# Dashboard_rev5.net
KiCad netlist of a schematic drawn in EAGLE
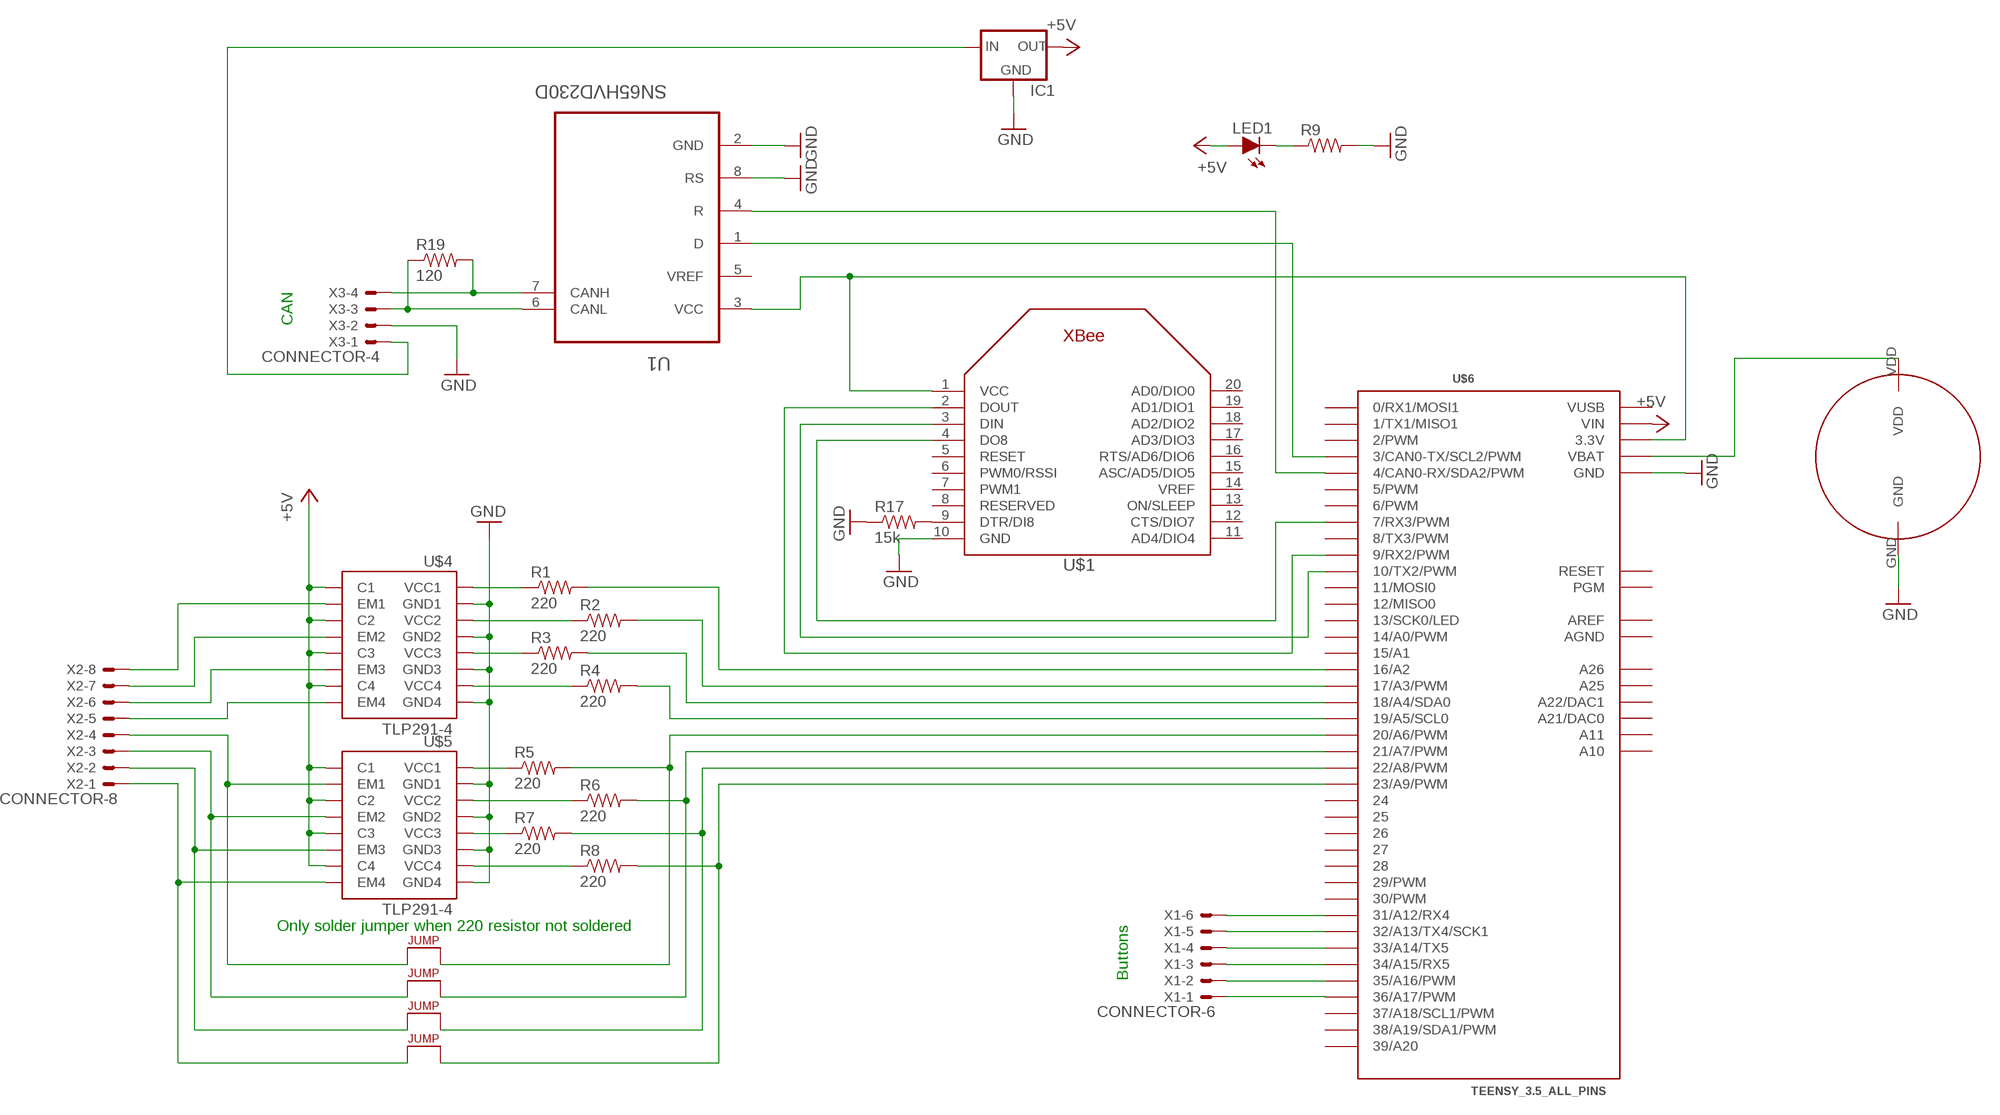
[diagram p0: schematic, sheet 1]

(export (version "E")
  (design (tool "Eeschema 10.0.6"))
  (components
    (comp (ref "BATT")
      (value "COIN-CELL-HOLDER")
      (footprint "eagle-import:COIN-CELL-HOLDER")
      (libsource (lib "eagle-import") (part "COIN-CELL-HOLDER"))
    )
    (comp (ref "IC1")
      (value "5VREG_L7805SPACED")
      (footprint "eagle-import:TO-220-SPACED")
      (libsource (lib "eagle-import") (part "5VREG_L7805SPACED"))
    )
    (comp (ref "LED1")
      (value "LED-0805")
      (footprint "eagle-import:LED-805")
      (libsource (lib "eagle-import") (part "LED-0805"))
    )
    (comp (ref "R1")
      (value "220")
      (footprint "eagle-import:0805")
      (libsource (lib "eagle-import") (part "RESISTOR0805-RES"))
    )
    (comp (ref "R2")
      (value "220")
      (footprint "eagle-import:0805")
      (libsource (lib "eagle-import") (part "RESISTOR0805-RES"))
    )
    (comp (ref "R3")
      (value "220")
      (footprint "eagle-import:0805")
      (libsource (lib "eagle-import") (part "RESISTOR0805-RES"))
    )
    (comp (ref "R4")
      (value "220")
      (footprint "eagle-import:0805")
      (libsource (lib "eagle-import") (part "RESISTOR0805-RES"))
    )
    (comp (ref "R5")
      (value "220")
      (footprint "eagle-import:0805")
      (libsource (lib "eagle-import") (part "RESISTOR0805-RES"))
    )
    (comp (ref "R6")
      (value "220")
      (footprint "eagle-import:0805")
      (libsource (lib "eagle-import") (part "RESISTOR0805-RES"))
    )
    (comp (ref "R7")
      (value "220")
      (footprint "eagle-import:0805")
      (libsource (lib "eagle-import") (part "RESISTOR0805-RES"))
    )
    (comp (ref "R8")
      (value "220")
      (footprint "eagle-import:0805")
      (libsource (lib "eagle-import") (part "RESISTOR0805-RES"))
    )
    (comp (ref "R9")
      (value "RESISTOR0805-RES")
      (footprint "eagle-import:0805")
      (libsource (lib "eagle-import") (part "RESISTOR0805-RES"))
    )
    (comp (ref "R17")
      (value "15k")
      (footprint "eagle-import:0805")
      (libsource (lib "eagle-import") (part "RESISTOR0805-RES"))
    )
    (comp (ref "R19")
      (value "120")
      (footprint "eagle-import:0805")
      (libsource (lib "eagle-import") (part "RESISTOR0805-RES"))
    )
    (comp (ref "U$1")
      (value "XBEE")
      (footprint "eagle-import:XBEE")
      (libsource (lib "eagle-import") (part "XBEE"))
    )
    (comp (ref "U$3")
      (value "JUMPER")
      (footprint "eagle-import:0805")
      (libsource (lib "eagle-import") (part "JUMPER"))
    )
    (comp (ref "U$4")
      (value "TLP291-4")
      (footprint "eagle-import:SOIC-16")
      (libsource (lib "eagle-import") (part "TLP291-4"))
    )
    (comp (ref "U$5")
      (value "TLP291-4")
      (footprint "eagle-import:SOIC-16")
      (libsource (lib "eagle-import") (part "TLP291-4"))
    )
    (comp (ref "U$6")
      (value "TEENSY_3.5_ALL_PINS")
      (footprint "eagle-import:TEENSY_3.5_ALL_PINS")
      (libsource (lib "eagle-import") (part "TEENSY_3.5_ALL_PINS"))
    )
    (comp (ref "U$7")
      (value "JUMPER")
      (footprint "eagle-import:0805")
      (libsource (lib "eagle-import") (part "JUMPER"))
    )
    (comp (ref "U$8")
      (value "JUMPER")
      (footprint "eagle-import:0805")
      (libsource (lib "eagle-import") (part "JUMPER"))
    )
    (comp (ref "U$9")
      (value "JUMPER")
      (footprint "eagle-import:0805")
      (libsource (lib "eagle-import") (part "JUMPER"))
    )
    (comp (ref "U1")
      (value "SN65HVD230D")
      (footprint "eagle-import:SOIC127P600X175-8N")
      (libsource (lib "eagle-import") (part "SN65HVD230D"))
    )
    (comp (ref "X1")
      (value "CONNECTOR-6")
      (footprint "eagle-import:MINIFIT_5566-6")
      (fields (field (name "MPN") "95566-61002"))
      (libsource (lib "eagle-import") (part "CONNECTOR-6"))
    )
    (comp (ref "X2")
      (value "CONNECTOR-8")
      (footprint "eagle-import:MINIFIT_5566-8")
      (libsource (lib "eagle-import") (part "CONNECTOR-8"))
    )
    (comp (ref "X3")
      (value "CONNECTOR-4")
      (footprint "eagle-import:MINIFIT_5566-4")
      (libsource (lib "eagle-import") (part "CONNECTOR-4"))
    )
  )
  (nets
    (net (code "1") (name "+5V") (class "Default")
      (node (ref "IC1") (pin "3") (pinfunction "OUT_3") (pintype "output"))
      (node (ref "LED1") (pin "A") (pinfunction "A_A") (pintype "passive"))
      (node (ref "U$4") (pin "10") (pinfunction "C4_10") (pintype "passive"))
      (node (ref "U$4") (pin "12") (pinfunction "C3_12") (pintype "passive"))
      (node (ref "U$4") (pin "14") (pinfunction "C2_14") (pintype "passive"))
      (node (ref "U$4") (pin "16") (pinfunction "C1_16") (pintype "passive"))
      (node (ref "U$5") (pin "10") (pinfunction "C4_10") (pintype "passive"))
      (node (ref "U$5") (pin "12") (pinfunction "C3_12") (pintype "passive"))
      (node (ref "U$5") (pin "14") (pinfunction "C2_14") (pintype "passive"))
      (node (ref "U$5") (pin "16") (pinfunction "C1_16") (pintype "passive"))
      (node (ref "U$6") (pin "VIN") (pinfunction "VIN_VIN") (pintype "power_in"))
    )
    (net (code "2") (name "/AGND") (class "Default")
      (node (ref "U$6") (pin "AGND") (pinfunction "AGND_AGND") (pintype "power_in"))
    )
    (net (code "3") (name "/AREF") (class "Default")
      (node (ref "U$6") (pin "AREF") (pinfunction "AREF_AREF") (pintype "power_in"))
    )
    (net (code "4") (name "/VUSB") (class "Default")
      (node (ref "U$6") (pin "VUSB") (pinfunction "VUSB_VUSB") (pintype "power_in"))
    )
    (net (code "5") (name "GND") (class "Default")
      (node (ref "BATT") (pin "GND") (pinfunction "GND_GND") (pintype "bidirectional"))
      (node (ref "IC1") (pin "2") (pinfunction "GND_2") (pintype "input"))
      (node (ref "R17") (pin "1") (pinfunction "1_1") (pintype "passive"))
      (node (ref "R9") (pin "2") (pinfunction "2_2") (pintype "passive"))
      (node (ref "U$1") (pin "10") (pinfunction "GND_10") (pintype "power_in"))
      (node (ref "U$4") (pin "2") (pinfunction "GND1_2") (pintype "passive"))
      (node (ref "U$4") (pin "4") (pinfunction "GND2_4") (pintype "passive"))
      (node (ref "U$4") (pin "6") (pinfunction "GND3_6") (pintype "passive"))
      (node (ref "U$4") (pin "8") (pinfunction "GND4_8") (pintype "passive"))
      (node (ref "U$5") (pin "2") (pinfunction "GND1_2") (pintype "passive"))
      (node (ref "U$5") (pin "4") (pinfunction "GND2_4") (pintype "passive"))
      (node (ref "U$5") (pin "6") (pinfunction "GND3_6") (pintype "passive"))
      (node (ref "U$5") (pin "8") (pinfunction "GND4_8") (pintype "passive"))
      (node (ref "U$6") (pin "GND") (pinfunction "GND_GND") (pintype "power_in"))
      (node (ref "U$6") (pin "GND1") (pinfunction "GND_GND1") (pintype "power_in"))
      (node (ref "U$6") (pin "GND3") (pinfunction "GND_GND3") (pintype "power_in"))
      (node (ref "U$6") (pin "GND4") (pinfunction "GND_GND4") (pintype "power_in"))
      (node (ref "U$6") (pin "GND6") (pinfunction "GND_GND6") (pintype "power_in"))
      (node (ref "U1") (pin "2") (pinfunction "GND_2") (pintype "passive"))
      (node (ref "U1") (pin "8") (pinfunction "RS_8") (pintype "input"))
      (node (ref "X3") (pin "2") (pinfunction "S_2") (pintype "passive"))
    )
    (net (code "6") (name "Net-(BATT-PadVDD)") (class "Default")
      (node (ref "BATT") (pin "VDD") (pinfunction "VDD_VDD") (pintype "bidirectional"))
      (node (ref "U$6") (pin "VBAT") (pinfunction "VBAT_VBAT") (pintype "power_in"))
    )
    (net (code "7") (name "Net-(IC1-IN)") (class "Default")
      (node (ref "IC1") (pin "1") (pinfunction "IN_1") (pintype "input"))
      (node (ref "X3") (pin "1") (pinfunction "S_1") (pintype "passive"))
    )
    (net (code "8") (name "Net-(LED1-PadC)") (class "Default")
      (node (ref "LED1") (pin "C") (pinfunction "C_C") (pintype "passive"))
      (node (ref "R9") (pin "1") (pinfunction "1_1") (pintype "passive"))
    )
    (net (code "9") (name "Net-(R1-Pad2)") (class "Default")
      (node (ref "R1") (pin "2") (pinfunction "2_2") (pintype "passive"))
      (node (ref "U$6") (pin "16/A2") (pinfunction "16/A2_16/A2") (pintype "bidirectional"))
    )
    (net (code "10") (name "Net-(U$1-DIN)") (class "Default")
      (node (ref "U$1") (pin "3") (pinfunction "DIN_3") (pintype "input"))
      (node (ref "U$6") (pin "10") (pinfunction "10/TX2/PWM_10") (pintype "bidirectional"))
    )
    (net (code "11") (name "Net-(U$1-DO8)") (class "Default")
      (node (ref "U$1") (pin "4") (pinfunction "DO8_4") (pintype "output"))
      (node (ref "U$6") (pin "7") (pinfunction "7/RX3/PWM_7") (pintype "bidirectional"))
    )
    (net (code "12") (name "Net-(U$1-DOUT)") (class "Default")
      (node (ref "U$1") (pin "2") (pinfunction "DOUT_2") (pintype "output"))
      (node (ref "U$6") (pin "9") (pinfunction "9/RX2/PWM_9") (pintype "bidirectional"))
    )
    (net (code "13") (name "Net-(U$1-DTR{slash}DI8)") (class "Default")
      (node (ref "R17") (pin "2") (pinfunction "2_2") (pintype "passive"))
      (node (ref "U$1") (pin "9") (pinfunction "DTR/DI8_9") (pintype "input"))
    )
    (net (code "14") (name "Net-(U$1-VCC)") (class "Default")
      (node (ref "U$1") (pin "1") (pinfunction "VCC_1") (pintype "power_in"))
      (node (ref "U$6") (pin "3.3V") (pinfunction "3.3V_3.3V") (pintype "power_in"))
      (node (ref "U$6") (pin "3.3V3") (pinfunction "3.3V_3.3V3") (pintype "power_in"))
      (node (ref "U$6") (pin "3.3V4") (pinfunction "3.3V_3.3V4") (pintype "power_in"))
      (node (ref "U1") (pin "3") (pinfunction "VCC_3") (pintype "power_in"))
    )
    (net (code "15") (name "Net-(U$3-P$1)") (class "Default")
      (node (ref "U$3") (pin "1") (pinfunction "P$1_1") (pintype "bidirectional"))
      (node (ref "U$5") (pin "15") (pinfunction "EM1_15") (pintype "passive"))
      (node (ref "X2") (pin "4") (pinfunction "S_4") (pintype "passive"))
    )
    (net (code "16") (name "Net-(U$3-P$2)") (class "Default")
      (node (ref "R5") (pin "2") (pinfunction "2_2") (pintype "passive"))
      (node (ref "U$3") (pin "2") (pinfunction "P$2_2") (pintype "bidirectional"))
      (node (ref "U$6") (pin "20/A6") (pinfunction "20/A6/PWM_20/A6") (pintype "bidirectional"))
    )
    (net (code "17") (name "Net-(U$4-EM1)") (class "Default")
      (node (ref "U$4") (pin "15") (pinfunction "EM1_15") (pintype "passive"))
      (node (ref "X2") (pin "8") (pinfunction "S_8") (pintype "passive"))
    )
    (net (code "18") (name "Net-(U$4-EM2)") (class "Default")
      (node (ref "U$4") (pin "13") (pinfunction "EM2_13") (pintype "passive"))
      (node (ref "X2") (pin "7") (pinfunction "S_7") (pintype "passive"))
    )
    (net (code "19") (name "Net-(U$4-EM3)") (class "Default")
      (node (ref "U$4") (pin "11") (pinfunction "EM3_11") (pintype "passive"))
      (node (ref "X2") (pin "6") (pinfunction "S_6") (pintype "passive"))
    )
    (net (code "20") (name "Net-(U$4-EM4)") (class "Default")
      (node (ref "U$4") (pin "9") (pinfunction "EM4_9") (pintype "passive"))
      (node (ref "X2") (pin "5") (pinfunction "S_5") (pintype "passive"))
    )
    (net (code "21") (name "Net-(U$4-VCC1)") (class "Default")
      (node (ref "R1") (pin "1") (pinfunction "1_1") (pintype "passive"))
      (node (ref "U$4") (pin "1") (pinfunction "VCC1_1") (pintype "passive"))
    )
    (net (code "22") (name "Net-(U$4-VCC2)") (class "Default")
      (node (ref "R2") (pin "1") (pinfunction "1_1") (pintype "passive"))
      (node (ref "U$4") (pin "3") (pinfunction "VCC2_3") (pintype "passive"))
    )
    (net (code "23") (name "Net-(U$4-VCC3)") (class "Default")
      (node (ref "R3") (pin "1") (pinfunction "1_1") (pintype "passive"))
      (node (ref "U$4") (pin "5") (pinfunction "VCC3_5") (pintype "passive"))
    )
    (net (code "24") (name "Net-(U$4-VCC4)") (class "Default")
      (node (ref "R4") (pin "1") (pinfunction "1_1") (pintype "passive"))
      (node (ref "U$4") (pin "7") (pinfunction "VCC4_7") (pintype "passive"))
    )
    (net (code "25") (name "Net-(U$5-EM2)") (class "Default")
      (node (ref "U$5") (pin "13") (pinfunction "EM2_13") (pintype "passive"))
      (node (ref "U$7") (pin "1") (pinfunction "P$1_1") (pintype "bidirectional"))
      (node (ref "X2") (pin "3") (pinfunction "S_3") (pintype "passive"))
    )
    (net (code "26") (name "Net-(U$5-EM3)") (class "Default")
      (node (ref "U$5") (pin "11") (pinfunction "EM3_11") (pintype "passive"))
      (node (ref "U$8") (pin "1") (pinfunction "P$1_1") (pintype "bidirectional"))
      (node (ref "X2") (pin "2") (pinfunction "S_2") (pintype "passive"))
    )
    (net (code "27") (name "Net-(U$5-EM4)") (class "Default")
      (node (ref "U$5") (pin "9") (pinfunction "EM4_9") (pintype "passive"))
      (node (ref "U$9") (pin "1") (pinfunction "P$1_1") (pintype "bidirectional"))
      (node (ref "X2") (pin "1") (pinfunction "S_1") (pintype "passive"))
    )
    (net (code "28") (name "Net-(U$5-VCC1)") (class "Default")
      (node (ref "R5") (pin "1") (pinfunction "1_1") (pintype "passive"))
      (node (ref "U$5") (pin "1") (pinfunction "VCC1_1") (pintype "passive"))
    )
    (net (code "29") (name "Net-(U$5-VCC2)") (class "Default")
      (node (ref "R6") (pin "1") (pinfunction "1_1") (pintype "passive"))
      (node (ref "U$5") (pin "3") (pinfunction "VCC2_3") (pintype "passive"))
    )
    (net (code "30") (name "Net-(U$5-VCC3)") (class "Default")
      (node (ref "R7") (pin "1") (pinfunction "1_1") (pintype "passive"))
      (node (ref "U$5") (pin "5") (pinfunction "VCC3_5") (pintype "passive"))
    )
    (net (code "31") (name "Net-(U$5-VCC4)") (class "Default")
      (node (ref "R8") (pin "1") (pinfunction "1_1") (pintype "passive"))
      (node (ref "U$5") (pin "7") (pinfunction "VCC4_7") (pintype "passive"))
    )
    (net (code "32") (name "Net-(U$6-3{slash}CAN0-TX{slash}SCL2{slash}PWM)") (class "Default")
      (node (ref "U$6") (pin "3") (pinfunction "3/CAN0-TX/SCL2/PWM_3") (pintype "bidirectional"))
      (node (ref "U1") (pin "1") (pinfunction "D_1") (pintype "input"))
    )
    (net (code "33") (name "Net-(U$6-4{slash}CAN0-RX{slash}SDA2{slash}PWM)") (class "Default")
      (node (ref "U$6") (pin "4") (pinfunction "4/CAN0-RX/SDA2/PWM_4") (pintype "bidirectional"))
      (node (ref "U1") (pin "4") (pinfunction "R_4") (pintype "input"))
    )
    (net (code "34") (name "Net-(U$6-17{slash}A3{slash}PWM)") (class "Default")
      (node (ref "R2") (pin "2") (pinfunction "2_2") (pintype "passive"))
      (node (ref "U$6") (pin "17/A3") (pinfunction "17/A3/PWM_17/A3") (pintype "bidirectional"))
    )
    (net (code "35") (name "Net-(U$6-18{slash}A4{slash}SDA0)") (class "Default")
      (node (ref "R3") (pin "2") (pinfunction "2_2") (pintype "passive"))
      (node (ref "U$6") (pin "18/A4") (pinfunction "18/A4/SDA0_18/A4") (pintype "bidirectional"))
    )
    (net (code "36") (name "Net-(U$6-19{slash}A5{slash}SCL0)") (class "Default")
      (node (ref "R4") (pin "2") (pinfunction "2_2") (pintype "passive"))
      (node (ref "U$6") (pin "19/A5") (pinfunction "19/A5/SCL0_19/A5") (pintype "bidirectional"))
    )
    (net (code "37") (name "Net-(U$6-21{slash}A7{slash}PWM)") (class "Default")
      (node (ref "R6") (pin "2") (pinfunction "2_2") (pintype "passive"))
      (node (ref "U$6") (pin "21/A7") (pinfunction "21/A7/PWM_21/A7") (pintype "bidirectional"))
      (node (ref "U$7") (pin "2") (pinfunction "P$2_2") (pintype "bidirectional"))
    )
    (net (code "38") (name "Net-(U$6-22{slash}A8{slash}PWM)") (class "Default")
      (node (ref "R7") (pin "2") (pinfunction "2_2") (pintype "passive"))
      (node (ref "U$6") (pin "22/A8") (pinfunction "22/A8/PWM_22/A8") (pintype "bidirectional"))
      (node (ref "U$8") (pin "2") (pinfunction "P$2_2") (pintype "bidirectional"))
    )
    (net (code "39") (name "Net-(U$6-23{slash}A9{slash}PWM)") (class "Default")
      (node (ref "R8") (pin "2") (pinfunction "2_2") (pintype "passive"))
      (node (ref "U$6") (pin "23/A9") (pinfunction "23/A9/PWM_23/A9") (pintype "bidirectional"))
      (node (ref "U$9") (pin "2") (pinfunction "P$2_2") (pintype "bidirectional"))
    )
    (net (code "40") (name "Net-(U$6-31{slash}A12{slash}RX4)") (class "Default")
      (node (ref "U$6") (pin "31/A12") (pinfunction "31/A12/RX4_31/A12") (pintype "bidirectional"))
      (node (ref "X1") (pin "6") (pinfunction "S_6") (pintype "passive"))
    )
    (net (code "41") (name "Net-(U$6-32{slash}A13{slash}TX4{slash}SCK1)") (class "Default")
      (node (ref "U$6") (pin "32/A13") (pinfunction "32/A13/TX4/SCK1_32/A13") (pintype "bidirectional"))
      (node (ref "X1") (pin "5") (pinfunction "S_5") (pintype "passive"))
    )
    (net (code "42") (name "Net-(U$6-33{slash}A14{slash}TX5)") (class "Default")
      (node (ref "U$6") (pin "33/A14") (pinfunction "33/A14/TX5_33/A14") (pintype "bidirectional"))
      (node (ref "X1") (pin "4") (pinfunction "S_4") (pintype "passive"))
    )
    (net (code "43") (name "Net-(U$6-34{slash}A15{slash}RX5)") (class "Default")
      (node (ref "U$6") (pin "34/A15") (pinfunction "34/A15/RX5_34/A15") (pintype "bidirectional"))
      (node (ref "X1") (pin "3") (pinfunction "S_3") (pintype "passive"))
    )
    (net (code "44") (name "Net-(U$6-35{slash}A16{slash}PWM)") (class "Default")
      (node (ref "U$6") (pin "35/A16") (pinfunction "35/A16/PWM_35/A16") (pintype "bidirectional"))
      (node (ref "X1") (pin "2") (pinfunction "S_2") (pintype "passive"))
    )
    (net (code "45") (name "Net-(U$6-36{slash}A17{slash}PWM)") (class "Default")
      (node (ref "U$6") (pin "36/A17") (pinfunction "36/A17/PWM_36/A17") (pintype "bidirectional"))
      (node (ref "X1") (pin "1") (pinfunction "S_1") (pintype "passive"))
    )
    (net (code "46") (name "Net-(U1-CANH)") (class "Default")
      (node (ref "R19") (pin "2") (pinfunction "2_2") (pintype "passive"))
      (node (ref "U1") (pin "7") (pinfunction "CANH_7") (pintype "output"))
      (node (ref "X3") (pin "4") (pinfunction "S_4") (pintype "passive"))
    )
    (net (code "47") (name "Net-(U1-CANL)") (class "Default")
      (node (ref "R19") (pin "1") (pinfunction "1_1") (pintype "passive"))
      (node (ref "U1") (pin "6") (pinfunction "CANL_6") (pintype "output"))
      (node (ref "X3") (pin "3") (pinfunction "S_3") (pintype "passive"))
    )
    (net (code "48") (name "unconnected-(U$1-AD0{slash}DIO0-Pad20)") (class "Default")
      (node (ref "U$1") (pin "20") (pinfunction "AD0/DIO0_20") (pintype "bidirectional"))
    )
    (net (code "49") (name "unconnected-(U$1-AD1{slash}DIO1-Pad19)") (class "Default")
      (node (ref "U$1") (pin "19") (pinfunction "AD1/DIO1_19") (pintype "bidirectional"))
    )
    (net (code "50") (name "unconnected-(U$1-AD2{slash}DIO2-Pad18)") (class "Default")
      (node (ref "U$1") (pin "18") (pinfunction "AD2/DIO2_18") (pintype "bidirectional"))
    )
    (net (code "51") (name "unconnected-(U$1-AD3{slash}DIO3-Pad17)") (class "Default")
      (node (ref "U$1") (pin "17") (pinfunction "AD3/DIO3_17") (pintype "bidirectional"))
    )
    (net (code "52") (name "unconnected-(U$1-AD4{slash}DIO4-Pad11)") (class "Default")
      (node (ref "U$1") (pin "11") (pinfunction "AD4/DIO4_11") (pintype "bidirectional"))
    )
    (net (code "53") (name "unconnected-(U$1-ASC{slash}AD5{slash}DIO5-Pad15)") (class "Default")
      (node (ref "U$1") (pin "15") (pinfunction "ASC/AD5/DIO5_15") (pintype "bidirectional"))
    )
    (net (code "54") (name "unconnected-(U$1-CTS{slash}DIO7-Pad12)") (class "Default")
      (node (ref "U$1") (pin "12") (pinfunction "CTS/DIO7_12") (pintype "bidirectional"))
    )
    (net (code "55") (name "unconnected-(U$1-ON{slash}SLEEP-Pad13)") (class "Default")
      (node (ref "U$1") (pin "13") (pinfunction "ON/SLEEP_13") (pintype "output"))
    )
    (net (code "56") (name "unconnected-(U$1-PWM0{slash}RSSI-Pad6)") (class "Default")
      (node (ref "U$1") (pin "6") (pinfunction "PWM0/RSSI_6") (pintype "output"))
    )
    (net (code "57") (name "unconnected-(U$1-PWM1-Pad7)") (class "Default")
      (node (ref "U$1") (pin "7") (pinfunction "PWM1_7") (pintype "output"))
    )
    (net (code "58") (name "unconnected-(U$1-RESERVED-Pad8)") (class "Default")
      (node (ref "U$1") (pin "8") (pinfunction "RESERVED_8") (pintype "no_connect"))
    )
    (net (code "59") (name "unconnected-(U$1-RESET-Pad5)") (class "Default")
      (node (ref "U$1") (pin "5") (pinfunction "RESET_5") (pintype "input"))
    )
    (net (code "60") (name "unconnected-(U$1-RTS{slash}AD6{slash}DIO6-Pad16)") (class "Default")
      (node (ref "U$1") (pin "16") (pinfunction "RTS/AD6/DIO6_16") (pintype "bidirectional"))
    )
    (net (code "61") (name "unconnected-(U$1-VREF-Pad14)") (class "Default")
      (node (ref "U$1") (pin "14") (pinfunction "VREF_14") (pintype "input"))
    )
    (net (code "62") (name "unconnected-(U$6-0{slash}RX1{slash}MOSI1-Pad0)") (class "Default")
      (node (ref "U$6") (pin "0") (pinfunction "0/RX1/MOSI1_0") (pintype "bidirectional"))
    )
    (net (code "63") (name "unconnected-(U$6-1{slash}TX1{slash}MISO1-Pad1)") (class "Default")
      (node (ref "U$6") (pin "1") (pinfunction "1/TX1/MISO1_1") (pintype "bidirectional"))
    )
    (net (code "64") (name "unconnected-(U$6-2{slash}PWM-Pad2)") (class "Default")
      (node (ref "U$6") (pin "2") (pinfunction "2/PWM_2") (pintype "bidirectional"))
    )
    (net (code "65") (name "unconnected-(U$6-5{slash}PWM-Pad5)") (class "Default")
      (node (ref "U$6") (pin "5") (pinfunction "5/PWM_5") (pintype "bidirectional"))
    )
    (net (code "66") (name "unconnected-(U$6-6{slash}PWM-Pad6)") (class "Default")
      (node (ref "U$6") (pin "6") (pinfunction "6/PWM_6") (pintype "bidirectional"))
    )
    (net (code "67") (name "unconnected-(U$6-8{slash}TX3{slash}PWM-Pad8)") (class "Default")
      (node (ref "U$6") (pin "8") (pinfunction "8/TX3/PWM_8") (pintype "bidirectional"))
    )
    (net (code "68") (name "unconnected-(U$6-11{slash}MOSI0-Pad11)") (class "Default")
      (node (ref "U$6") (pin "11") (pinfunction "11/MOSI0_11") (pintype "bidirectional"))
    )
    (net (code "69") (name "unconnected-(U$6-12{slash}MISO0-Pad12)") (class "Default")
      (node (ref "U$6") (pin "12") (pinfunction "12/MISO0_12") (pintype "bidirectional"))
    )
    (net (code "70") (name "unconnected-(U$6-13{slash}SCK0{slash}LED-Pad13)") (class "Default")
      (node (ref "U$6") (pin "13") (pinfunction "13/SCK0/LED_13") (pintype "bidirectional"))
    )
    (net (code "71") (name "unconnected-(U$6-14{slash}A0{slash}PWM-Pad14{slash}A0)") (class "Default")
      (node (ref "U$6") (pin "14/A0") (pinfunction "14/A0/PWM_14/A0") (pintype "bidirectional"))
    )
    (net (code "72") (name "unconnected-(U$6-29{slash}PWM-Pad29)") (class "Default")
      (node (ref "U$6") (pin "29") (pinfunction "29/PWM_29") (pintype "bidirectional"))
    )
    (net (code "73") (name "unconnected-(U$6-30{slash}PWM-Pad30)") (class "Default")
      (node (ref "U$6") (pin "30") (pinfunction "30/PWM_30") (pintype "bidirectional"))
    )
    (net (code "74") (name "unconnected-(U$6-37{slash}A18{slash}SCL1{slash}PWM-Pad37{slash}A18)") (class "Default")
      (node (ref "U$6") (pin "37/A18") (pinfunction "37/A18/SCL1/PWM_37/A18") (pintype "bidirectional"))
    )
    (net (code "75") (name "unconnected-(U$6-38{slash}A19{slash}SDA1{slash}PWM-Pad38{slash}A19)") (class "Default")
      (node (ref "U$6") (pin "38/A19") (pinfunction "38/A19/SDA1/PWM_38/A19") (pintype "bidirectional"))
    )
    (net (code "76") (name "unconnected-(U$6-A21{slash}DAC0-PadA21)") (class "Default")
      (node (ref "U$6") (pin "A21") (pinfunction "A21/DAC0_A21") (pintype "bidirectional"))
    )
    (net (code "77") (name "unconnected-(U$6-A22{slash}DAC1-PadA22)") (class "Default")
      (node (ref "U$6") (pin "A22") (pinfunction "A22/DAC1_A22") (pintype "bidirectional"))
    )
    (net (code "78") (name "unconnected-(U$6-Pad15{slash}A1)") (class "Default")
      (node (ref "U$6") (pin "15/A1") (pinfunction "15/A1_15/A1") (pintype "bidirectional"))
    )
    (net (code "79") (name "unconnected-(U$6-Pad24)") (class "Default")
      (node (ref "U$6") (pin "24") (pinfunction "24_24") (pintype "bidirectional"))
    )
    (net (code "80") (name "unconnected-(U$6-Pad25)") (class "Default")
      (node (ref "U$6") (pin "25") (pinfunction "25_25") (pintype "bidirectional"))
    )
    (net (code "81") (name "unconnected-(U$6-Pad26)") (class "Default")
      (node (ref "U$6") (pin "26") (pinfunction "26_26") (pintype "bidirectional"))
    )
    (net (code "82") (name "unconnected-(U$6-Pad27)") (class "Default")
      (node (ref "U$6") (pin "27") (pinfunction "27_27") (pintype "bidirectional"))
    )
    (net (code "83") (name "unconnected-(U$6-Pad28)") (class "Default")
      (node (ref "U$6") (pin "28") (pinfunction "28_28") (pintype "bidirectional"))
    )
    (net (code "84") (name "unconnected-(U$6-Pad39{slash}A20)") (class "Default")
      (node (ref "U$6") (pin "39/A20") (pinfunction "39/A20_39/A20") (pintype "bidirectional"))
    )
    (net (code "85") (name "unconnected-(U$6-PadA10)") (class "Default")
      (node (ref "U$6") (pin "A10") (pinfunction "A10_A10") (pintype "bidirectional"))
    )
    (net (code "86") (name "unconnected-(U$6-PadA11)") (class "Default")
      (node (ref "U$6") (pin "A11") (pinfunction "A11_A11") (pintype "bidirectional"))
    )
    (net (code "87") (name "unconnected-(U$6-PadA25)") (class "Default")
      (node (ref "U$6") (pin "A25") (pinfunction "A25_A25") (pintype "bidirectional"))
    )
    (net (code "88") (name "unconnected-(U$6-PadA26)") (class "Default")
      (node (ref "U$6") (pin "A26") (pinfunction "A26_A26") (pintype "bidirectional"))
    )
    (net (code "89") (name "unconnected-(U$6-PadPGM)") (class "Default")
      (node (ref "U$6") (pin "PGM") (pinfunction "PGM_PGM") (pintype "bidirectional"))
    )
    (net (code "90") (name "unconnected-(U$6-PadRESET)") (class "Default")
      (node (ref "U$6") (pin "RESET") (pinfunction "RESET_RESET") (pintype "bidirectional"))
    )
    (net (code "91") (name "unconnected-(U1-VREF-Pad5)") (class "Default")
      (node (ref "U1") (pin "5") (pinfunction "VREF_5") (pintype "input"))
    )
  )
)
